# Hypnos_V3.net
KiCad netlist of a schematic drawn in EAGLE
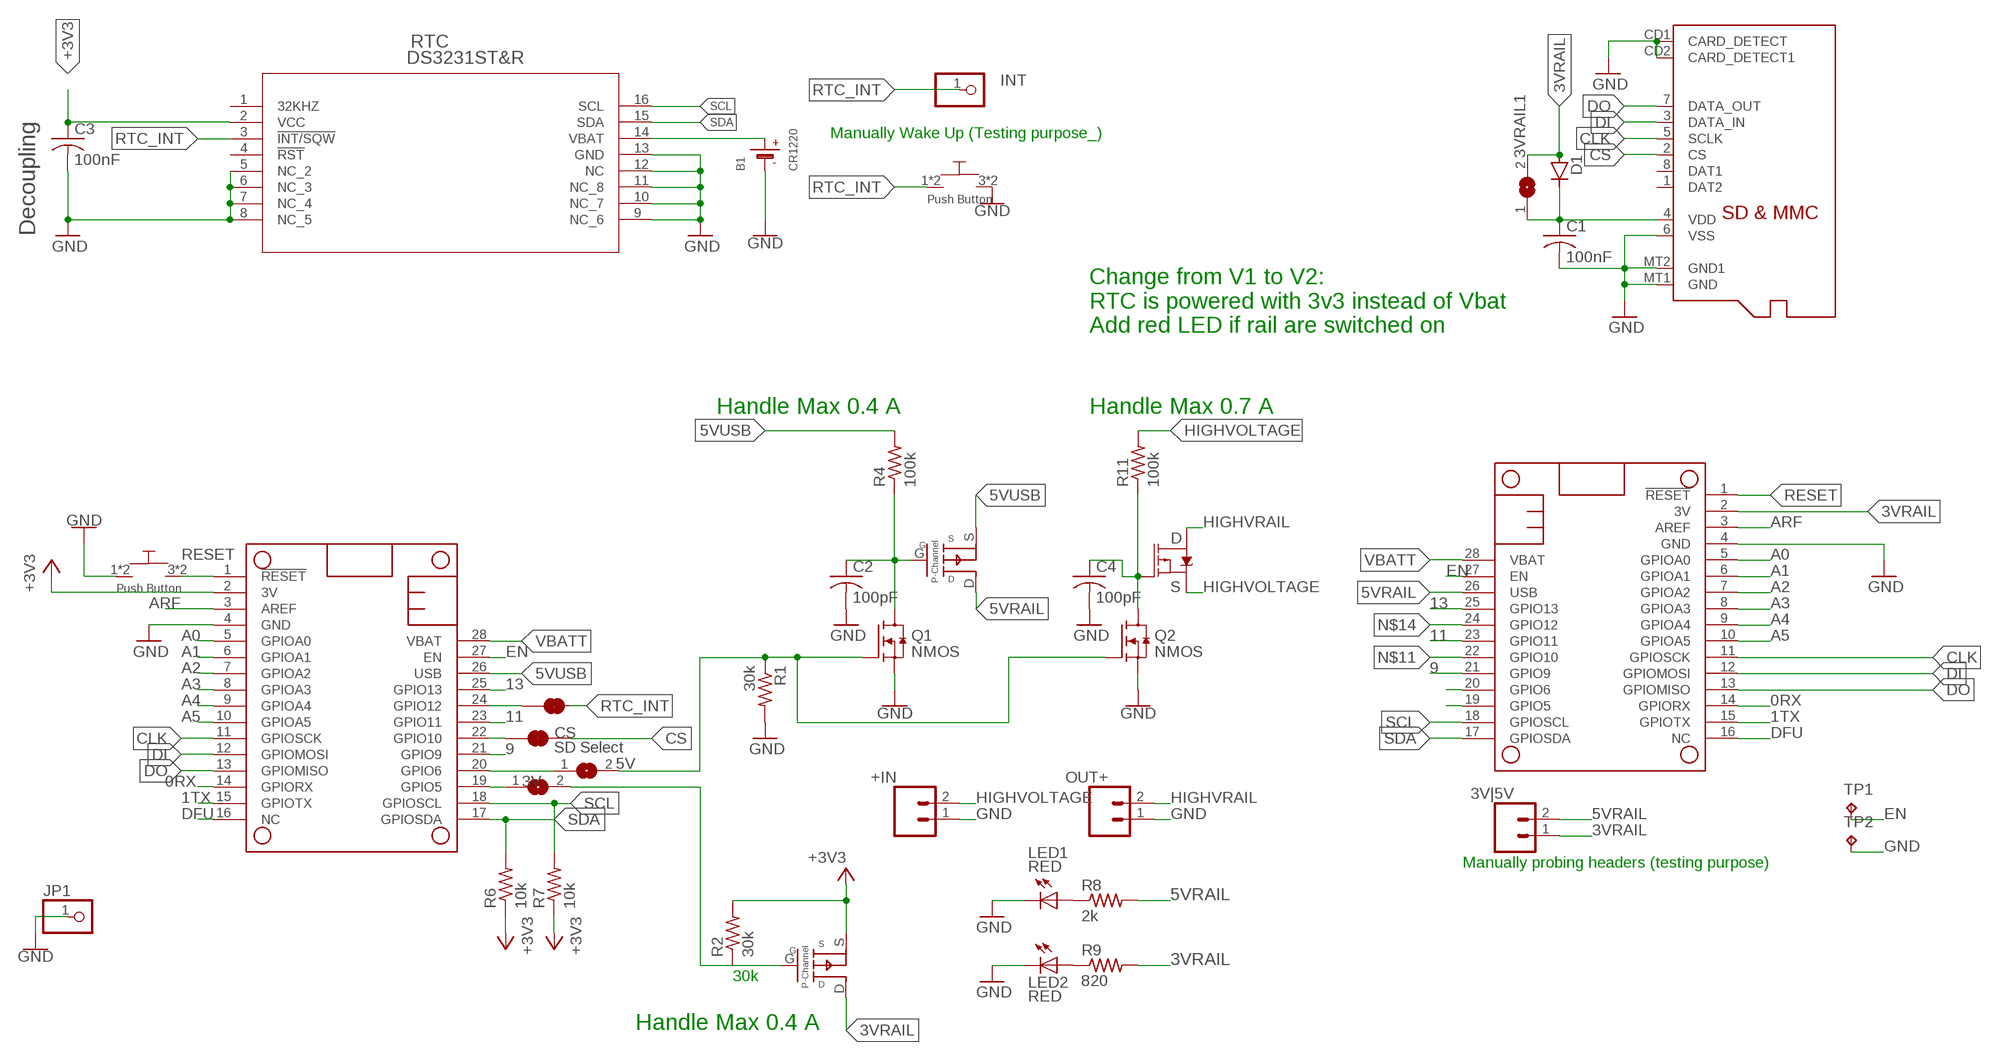
[diagram p0: schematic, sheet 1]

(export (version "E")
  (design (tool "Eeschema 10.0.6"))
  (components
    (comp (ref "+IN")
      (value "HIGHV-IN")
      (footprint "eagle-import:1X02_NO_SILK")
      (libsource (lib "eagle-import") (part "CONN_021X02_NO_SILK"))
    )
    (comp (ref "3V") (value "SJ") (footprint "eagle-import:SJ") (libsource (lib "eagle-import") (part "SJ")))
    (comp (ref "3VRAIL1")
      (value "SJ")
      (footprint "eagle-import:SJ")
      (libsource (lib "eagle-import") (part "SJ"))
    )
    (comp (ref "3V|5V")
      (value "CONN_021X02_NO_SILK")
      (footprint "eagle-import:1X02_NO_SILK")
      (libsource (lib "eagle-import") (part "CONN_021X02_NO_SILK"))
    )
    (comp (ref "5V") (value "SJ") (footprint "eagle-import:SJ") (libsource (lib "eagle-import") (part "SJ")))
    (comp (ref "B1")
      (value "CR1220")
      (footprint "eagle-import:CR1220")
      (libsource (lib "eagle-import") (part "BATTERYCR1220_SMT"))
    )
    (comp (ref "C1")
      (value "100nF")
      (footprint "eagle-import:C1206")
      (libsource (lib "eagle-import") (part "C-USC1206"))
    )
    (comp (ref "C2")
      (value "100pF")
      (footprint "eagle-import:C0805")
      (libsource (lib "eagle-import") (part "resistor_348_C-USC0805"))
    )
    (comp (ref "C3")
      (value "100nF")
      (footprint "eagle-import:C1206")
      (libsource (lib "eagle-import") (part "C-USC1206"))
    )
    (comp (ref "C4")
      (value "100pF")
      (footprint "eagle-import:C0805")
      (libsource (lib "eagle-import") (part "resistor_348_C-USC0805"))
    )
    (comp (ref "CS")
      (value "SD Select")
      (footprint "eagle-import:SMT-JUMPER_2_NC_TRACE_SILK")
      (libsource (lib "eagle-import") (part "JUMPER-SMT_2_NC_TRACE_SILK"))
    )
    (comp (ref "D1")
      (value "D-SOD123")
      (footprint "eagle-import:SOD123")
      (libsource (lib "eagle-import") (part "D-SOD123"))
    )
    (comp (ref "INT")
      (value "PINHD-1X1CB")
      (footprint "eagle-import:1X01-CLEANBIG")
      (libsource (lib "eagle-import") (part "PINHD-1X1CB"))
    )
    (comp (ref "JP1")
      (value "PINHD-1X1CB")
      (footprint "eagle-import:1X01-CLEANBIG")
      (libsource (lib "eagle-import") (part "PINHD-1X1CB"))
    )
    (comp (ref "LED1")
      (value "RED")
      (footprint "eagle-import:CHIPLED_0805")
      (libsource (lib "eagle-import") (part "LEDCHIPLED_0805"))
    )
    (comp (ref "LED2")
      (value "RED")
      (footprint "eagle-import:CHIPLED_0805")
      (libsource (lib "eagle-import") (part "LEDCHIPLED_0805"))
    )
    (comp (ref "MICROSD")
      (value "MICROSD")
      (footprint "eagle-import:MICROSD")
      (libsource (lib "eagle-import") (part "MICROSD"))
    )
    (comp (ref "MS1")
      (value "FEATHERWING")
      (footprint "eagle-import:FEATHERWING")
      (libsource (lib "eagle-import") (part "powerboard_FEATHERWING"))
    )
    (comp (ref "MS2")
      (value "FEATHERWING")
      (footprint "eagle-import:FEATHERWING")
      (libsource (lib "eagle-import") (part "FEATHERWING"))
    )
    (comp (ref "OUT+")
      (value "HIGHV-OUT")
      (footprint "eagle-import:1X02_NO_SILK")
      (libsource (lib "eagle-import") (part "CONN_021X02_NO_SILK"))
    )
    (comp (ref "PMOS1")
      (value "SSM3J3228R")
      (footprint "eagle-import:SOT-23-3")
      (libsource (lib "eagle-import") (part "SSM3J3228R"))
    )
    (comp (ref "PMOS2")
      (value "SSM3J3228R")
      (footprint "eagle-import:SOT-23-3")
      (libsource (lib "eagle-import") (part "SSM3J3228R"))
    )
    (comp (ref "PMOS3")
      (value "P-MOSFET")
      (footprint "eagle-import:SOT23-6")
      (libsource (lib "eagle-import") (part "P-MOSFET"))
    )
    (comp (ref "Q1")
      (value "NMOS")
      (footprint "eagle-import:SOT23-S")
      (libsource (lib "eagle-import") (part "NMOS"))
    )
    (comp (ref "Q2")
      (value "NMOS")
      (footprint "eagle-import:SOT23-S")
      (libsource (lib "eagle-import") (part "NMOS"))
    )
    (comp (ref "R1")
      (value "30k")
      (footprint "eagle-import:RES_1206")
      (fields
        (field (name "DIGIKEY_PART_NUMBER") "WSLP-.05TR-ND")
        (field (name "MANUFACTURER") "Vishay Dale")
        (field (name "MPN") "WSLP1206R0500FEA")
        (field (name "CREATED_BY") "PCBLayout.com")
      )
      (libsource (lib "eagle-import") (part "WSLP1206R0500FEA"))
    )
    (comp (ref "R2")
      (value "30k")
      (footprint "eagle-import:RES_1206")
      (fields
        (field (name "DIGIKEY_PART_NUMBER") "WSLP-.05TR-ND")
        (field (name "MANUFACTURER") "Vishay Dale")
        (field (name "MPN") "WSLP1206R0500FEA")
        (field (name "CREATED_BY") "PCBLayout.com")
      )
      (libsource (lib "eagle-import") (part "WSLP1206R0500FEA"))
    )
    (comp (ref "R4")
      (value "100k")
      (footprint "eagle-import:RES_1206")
      (fields
        (field (name "DIGIKEY_PART_NUMBER") "WSLP-.05TR-ND")
        (field (name "MANUFACTURER") "Vishay Dale")
        (field (name "MPN") "WSLP1206R0500FEA")
        (field (name "CREATED_BY") "PCBLayout.com")
      )
      (libsource (lib "eagle-import") (part "WSLP1206R0500FEA"))
    )
    (comp (ref "R6")
      (value "10k")
      (footprint "eagle-import:RES_1206")
      (fields
        (field (name "DIGIKEY_PART_NUMBER") "WSLP-.05TR-ND")
        (field (name "MANUFACTURER") "Vishay Dale")
        (field (name "MPN") "WSLP1206R0500FEA")
        (field (name "CREATED_BY") "PCBLayout.com")
      )
      (libsource (lib "eagle-import") (part "WSLP1206R0500FEA"))
    )
    (comp (ref "R7")
      (value "10k")
      (footprint "eagle-import:RES_1206")
      (fields
        (field (name "DIGIKEY_PART_NUMBER") "WSLP-.05TR-ND")
        (field (name "MANUFACTURER") "Vishay Dale")
        (field (name "MPN") "WSLP1206R0500FEA")
        (field (name "CREATED_BY") "PCBLayout.com")
      )
      (libsource (lib "eagle-import") (part "WSLP1206R0500FEA"))
    )
    (comp (ref "R8")
      (value "2k")
      (footprint "eagle-import:RES_1206")
      (fields
        (field (name "DIGIKEY_PART_NUMBER") "WSLP-.05TR-ND")
        (field (name "MANUFACTURER") "Vishay Dale")
        (field (name "MPN") "WSLP1206R0500FEA")
        (field (name "CREATED_BY") "PCBLayout.com")
      )
      (libsource (lib "eagle-import") (part "WSLP1206R0500FEA"))
    )
    (comp (ref "R9")
      (value "820")
      (footprint "eagle-import:RES_1206")
      (fields
        (field (name "DIGIKEY_PART_NUMBER") "WSLP-.05TR-ND")
        (field (name "MANUFACTURER") "Vishay Dale")
        (field (name "MPN") "WSLP1206R0500FEA")
        (field (name "CREATED_BY") "PCBLayout.com")
      )
      (libsource (lib "eagle-import") (part "WSLP1206R0500FEA"))
    )
    (comp (ref "R11")
      (value "100k")
      (footprint "eagle-import:RES_1206")
      (fields
        (field (name "DIGIKEY_PART_NUMBER") "WSLP-.05TR-ND")
        (field (name "MANUFACTURER") "Vishay Dale")
        (field (name "MPN") "WSLP1206R0500FEA")
        (field (name "CREATED_BY") "PCBLayout.com")
      )
      (libsource (lib "eagle-import") (part "WSLP1206R0500FEA"))
    )
    (comp (ref "RTC")
      (value "DS3231ST&R")
      (footprint "eagle-import:21-0042B_16")
      (fields (field (name "MANUFACTURER_PART_NUMBER") "DS3231S#T&R"))
      (libsource (lib "eagle-import") (part "DS3231ST&R"))
    )
    (comp (ref "RTC_INT")
      (value "JUMPER-SMT_2_NC_TRACE_SILK")
      (footprint "eagle-import:SMT-JUMPER_2_NC_TRACE_SILK")
      (libsource (lib "eagle-import") (part "JUMPER-SMT_2_NC_TRACE_SILK"))
    )
    (comp (ref "TP1")
      (value "TPTP16R")
      (footprint "eagle-import:TP16R")
      (libsource (lib "eagle-import") (part "TPTP16R"))
    )
    (comp (ref "TP2")
      (value "TPTP16R")
      (footprint "eagle-import:TP16R")
      (libsource (lib "eagle-import") (part "TPTP16R"))
    )
    (comp (ref "U$1")
      (value "PUSH_BUTTON")
      (footprint "eagle-import:PUSHBUTTON_SMD")
      (libsource (lib "eagle-import") (part "PUSH_BUTTON"))
    )
    (comp (ref "U$2")
      (value "PUSH_BUTTON")
      (footprint "eagle-import:PUSHBUTTON_SMD")
      (libsource (lib "eagle-import") (part "PUSH_BUTTON"))
    )
  )
  (nets
    (net (code "1") (name "+3V3") (class "Default")
      (node (ref "C3") (pin "1") (pinfunction "1_1") (pintype "passive"))
      (node (ref "MS2") (pin "2") (pinfunction "3V_2") (pintype "power_in"))
      (node (ref "PMOS2") (pin "S") (pinfunction "S_S") (pintype "bidirectional"))
      (node (ref "R2") (pin "2") (pinfunction "2_2") (pintype "passive"))
      (node (ref "R6") (pin "1") (pinfunction "1_1") (pintype "passive"))
      (node (ref "R7") (pin "1") (pinfunction "1_1") (pintype "passive"))
      (node (ref "RTC") (pin "2") (pinfunction "VCC_2") (pintype "power_in"))
    )
    (net (code "2") (name "/0RX") (class "Default")
      (node (ref "MS1") (pin "14") (pinfunction "GPIORX_14") (pintype "bidirectional"))
      (node (ref "MS2") (pin "14") (pinfunction "GPIORX_14") (pintype "bidirectional"))
    )
    (net (code "3") (name "/1TX") (class "Default")
      (node (ref "MS1") (pin "15") (pinfunction "GPIOTX_15") (pintype "bidirectional"))
      (node (ref "MS2") (pin "15") (pinfunction "GPIOTX_15") (pintype "bidirectional"))
    )
    (net (code "4") (name "/9") (class "Default")
      (node (ref "MS1") (pin "21") (pinfunction "GPIO9_21") (pintype "bidirectional"))
      (node (ref "MS2") (pin "21") (pinfunction "GPIO9_21") (pintype "bidirectional"))
    )
    (net (code "5") (name "/11") (class "Default")
      (node (ref "MS1") (pin "23") (pinfunction "GPIO11_23") (pintype "bidirectional"))
      (node (ref "MS2") (pin "23") (pinfunction "GPIO11_23") (pintype "bidirectional"))
    )
    (net (code "6") (name "/13") (class "Default")
      (node (ref "MS1") (pin "25") (pinfunction "GPIO13_25") (pintype "bidirectional"))
      (node (ref "MS2") (pin "25") (pinfunction "GPIO13_25") (pintype "bidirectional"))
    )
    (net (code "7") (name "/A0") (class "Default")
      (node (ref "MS1") (pin "5") (pinfunction "GPIOA0_5") (pintype "bidirectional"))
      (node (ref "MS2") (pin "5") (pinfunction "GPIOA0_5") (pintype "bidirectional"))
    )
    (net (code "8") (name "/A1") (class "Default")
      (node (ref "MS1") (pin "6") (pinfunction "GPIOA1_6") (pintype "bidirectional"))
      (node (ref "MS2") (pin "6") (pinfunction "GPIOA1_6") (pintype "bidirectional"))
    )
    (net (code "9") (name "/A2") (class "Default")
      (node (ref "MS1") (pin "7") (pinfunction "GPIOA2_7") (pintype "bidirectional"))
      (node (ref "MS2") (pin "7") (pinfunction "GPIOA2_7") (pintype "bidirectional"))
    )
    (net (code "10") (name "/A3") (class "Default")
      (node (ref "MS1") (pin "8") (pinfunction "GPIOA3_8") (pintype "bidirectional"))
      (node (ref "MS2") (pin "8") (pinfunction "GPIOA3_8") (pintype "bidirectional"))
    )
    (net (code "11") (name "/A4") (class "Default")
      (node (ref "MS1") (pin "9") (pinfunction "GPIOA4_9") (pintype "bidirectional"))
      (node (ref "MS2") (pin "9") (pinfunction "GPIOA4_9") (pintype "bidirectional"))
    )
    (net (code "12") (name "/A5") (class "Default")
      (node (ref "MS1") (pin "10") (pinfunction "GPIOA5_10") (pintype "bidirectional"))
      (node (ref "MS2") (pin "10") (pinfunction "GPIOA5_10") (pintype "bidirectional"))
    )
    (net (code "13") (name "/ARF") (class "Default")
      (node (ref "MS1") (pin "3") (pinfunction "AREF_3") (pintype "passive"))
      (node (ref "MS2") (pin "3") (pinfunction "AREF_3") (pintype "passive"))
    )
    (net (code "14") (name "/DFU") (class "Default")
      (node (ref "MS1") (pin "16") (pinfunction "NC_16") (pintype "passive"))
      (node (ref "MS2") (pin "16") (pinfunction "NC_16") (pintype "passive"))
    )
    (net (code "15") (name "/EN") (class "Default")
      (node (ref "MS1") (pin "27") (pinfunction "EN_27") (pintype "passive"))
      (node (ref "MS2") (pin "27") (pinfunction "EN_27") (pintype "passive"))
      (node (ref "TP1") (pin "TP") (pinfunction "TP_TP") (pintype "input"))
    )
    (net (code "16") (name "/HIGHVRAIL") (class "Default")
      (node (ref "OUT+") (pin "2") (pinfunction "2_2") (pintype "passive"))
      (node (ref "PMOS3") (pin "1") (pinfunction "D_1") (pintype "bidirectional"))
      (node (ref "PMOS3") (pin "2") (pinfunction "D_2") (pintype "bidirectional"))
      (node (ref "PMOS3") (pin "5") (pinfunction "D_5") (pintype "bidirectional"))
      (node (ref "PMOS3") (pin "6") (pinfunction "D_6") (pintype "bidirectional"))
    )
    (net (code "17") (name "3VRAIL") (class "Default")
      (node (ref "3VRAIL1") (pin "2") (pinfunction "2_2") (pintype "passive"))
      (node (ref "3V|5V") (pin "1") (pinfunction "1_1") (pintype "passive"))
      (node (ref "D1") (pin "2") (pinfunction "A_2") (pintype "passive"))
      (node (ref "MS1") (pin "2") (pinfunction "3V_2") (pintype "power_in"))
      (node (ref "PMOS2") (pin "D") (pinfunction "D_D") (pintype "bidirectional"))
      (node (ref "R9") (pin "2") (pinfunction "2_2") (pintype "passive"))
    )
    (net (code "18") (name "5VRAIL") (class "Default")
      (node (ref "3V|5V") (pin "2") (pinfunction "2_2") (pintype "passive"))
      (node (ref "MS1") (pin "26") (pinfunction "USB_26") (pintype "power_in"))
      (node (ref "PMOS1") (pin "D") (pinfunction "D_D") (pintype "bidirectional"))
      (node (ref "R8") (pin "2") (pinfunction "2_2") (pintype "passive"))
    )
    (net (code "19") (name "5VUSB") (class "Default")
      (node (ref "MS2") (pin "26") (pinfunction "USB_26") (pintype "power_in"))
      (node (ref "PMOS1") (pin "S") (pinfunction "S_S") (pintype "bidirectional"))
      (node (ref "R4") (pin "2") (pinfunction "2_2") (pintype "passive"))
    )
    (net (code "20") (name "CLK") (class "Default")
      (node (ref "MICROSD") (pin "5") (pinfunction "SCLK_5") (pintype "input"))
      (node (ref "MS1") (pin "11") (pinfunction "GPIOSCK_11") (pintype "bidirectional"))
      (node (ref "MS2") (pin "11") (pinfunction "GPIOSCK_11") (pintype "bidirectional"))
    )
    (net (code "21") (name "CS") (class "Default")
      (node (ref "CS") (pin "2") (pinfunction "2_2") (pintype "passive"))
      (node (ref "MICROSD") (pin "2") (pinfunction "CS_2") (pintype "input"))
    )
    (net (code "22") (name "DI") (class "Default")
      (node (ref "MICROSD") (pin "3") (pinfunction "DATA_IN_3") (pintype "input"))
      (node (ref "MS1") (pin "12") (pinfunction "GPIOMOSI_12") (pintype "bidirectional"))
      (node (ref "MS2") (pin "12") (pinfunction "GPIOMOSI_12") (pintype "bidirectional"))
    )
    (net (code "23") (name "DO") (class "Default")
      (node (ref "MICROSD") (pin "7") (pinfunction "DATA_OUT_7") (pintype "output"))
      (node (ref "MS1") (pin "13") (pinfunction "GPIOMISO_13") (pintype "bidirectional"))
      (node (ref "MS2") (pin "13") (pinfunction "GPIOMISO_13") (pintype "bidirectional"))
    )
    (net (code "24") (name "GND") (class "Default")
      (node (ref "+IN") (pin "1") (pinfunction "1_1") (pintype "passive"))
      (node (ref "B1") (pin "-") (pinfunction "-_-") (pintype "passive"))
      (node (ref "C1") (pin "2") (pinfunction "2_2") (pintype "passive"))
      (node (ref "C2") (pin "2") (pinfunction "2_2") (pintype "passive"))
      (node (ref "C3") (pin "2") (pinfunction "2_2") (pintype "passive"))
      (node (ref "C4") (pin "2") (pinfunction "2_2") (pintype "passive"))
      (node (ref "JP1") (pin "1") (pinfunction "1_1") (pintype "passive"))
      (node (ref "LED1") (pin "C") (pinfunction "C_C") (pintype "passive"))
      (node (ref "LED2") (pin "C") (pinfunction "C_C") (pintype "passive"))
      (node (ref "MICROSD") (pin "6") (pinfunction "VSS_6") (pintype "power_in"))
      (node (ref "MICROSD") (pin "CD1") (pinfunction "CARD_DETECT_CD1") (pintype "passive"))
      (node (ref "MICROSD") (pin "CD2") (pinfunction "CARD_DETECT1_CD2") (pintype "passive"))
      (node (ref "MICROSD") (pin "MT1") (pinfunction "GND_MT1") (pintype "power_in"))
      (node (ref "MICROSD") (pin "MT2") (pinfunction "GND1_MT2") (pintype "power_in"))
      (node (ref "MS1") (pin "4") (pinfunction "GND_4") (pintype "power_in"))
      (node (ref "MS2") (pin "4") (pinfunction "GND_4") (pintype "power_in"))
      (node (ref "OUT+") (pin "1") (pinfunction "1_1") (pintype "passive"))
      (node (ref "Q1") (pin "2") (pinfunction "S_2") (pintype "passive"))
      (node (ref "Q2") (pin "2") (pinfunction "S_2") (pintype "passive"))
      (node (ref "R1") (pin "2") (pinfunction "2_2") (pintype "passive"))
      (node (ref "RTC") (pin "10") (pinfunction "NC_7_10") (pintype "passive"))
      (node (ref "RTC") (pin "11") (pinfunction "NC_8_11") (pintype "passive"))
      (node (ref "RTC") (pin "12") (pinfunction "NC_12") (pintype "passive"))
      (node (ref "RTC") (pin "13") (pinfunction "GND_13") (pintype "power_in"))
      (node (ref "RTC") (pin "5") (pinfunction "NC_2_5") (pintype "passive"))
      (node (ref "RTC") (pin "6") (pinfunction "NC_3_6") (pintype "passive"))
      (node (ref "RTC") (pin "7") (pinfunction "NC_4_7") (pintype "passive"))
      (node (ref "RTC") (pin "8") (pinfunction "NC_5_8") (pintype "passive"))
      (node (ref "RTC") (pin "9") (pinfunction "NC_6_9") (pintype "passive"))
      (node (ref "TP2") (pin "TP") (pinfunction "TP_TP") (pintype "input"))
      (node (ref "U$1") (pin "1") (pinfunction "P$1_1") (pintype "bidirectional"))
      (node (ref "U$1") (pin "2") (pinfunction "P$1_2") (pintype "bidirectional"))
      (node (ref "U$2") (pin "3") (pinfunction "P$2_3") (pintype "bidirectional"))
      (node (ref "U$2") (pin "4") (pinfunction "P$2_4") (pintype "bidirectional"))
    )
    (net (code "25") (name "HIGHVOLTAGE") (class "Default")
      (node (ref "+IN") (pin "2") (pinfunction "2_2") (pintype "passive"))
      (node (ref "PMOS3") (pin "4") (pinfunction "S_4") (pintype "bidirectional"))
      (node (ref "R11") (pin "2") (pinfunction "2_2") (pintype "passive"))
    )
    (net (code "26") (name "N$11") (class "Default")
      (node (ref "CS") (pin "1") (pinfunction "1_1") (pintype "passive"))
      (node (ref "MS1") (pin "22") (pinfunction "GPIO10_22") (pintype "bidirectional"))
      (node (ref "MS2") (pin "22") (pinfunction "GPIO10_22") (pintype "bidirectional"))
    )
    (net (code "27") (name "N$14") (class "Default")
      (node (ref "MS1") (pin "24") (pinfunction "GPIO12_24") (pintype "bidirectional"))
      (node (ref "MS2") (pin "24") (pinfunction "GPIO12_24") (pintype "bidirectional"))
      (node (ref "RTC_INT") (pin "1") (pinfunction "1_1") (pintype "passive"))
    )
    (net (code "28") (name "Net-(3V-Pad2)") (class "Default")
      (node (ref "3V") (pin "2") (pinfunction "2_2") (pintype "passive"))
      (node (ref "PMOS2") (pin "G") (pinfunction "G_G") (pintype "bidirectional"))
      (node (ref "R2") (pin "1") (pinfunction "1_1") (pintype "passive"))
    )
    (net (code "29") (name "Net-(B1-+)") (class "Default")
      (node (ref "B1") (pin "+$1") (pinfunction "+_+$1") (pintype "passive"))
      (node (ref "RTC") (pin "14") (pinfunction "VBAT_14") (pintype "power_in"))
    )
    (net (code "30") (name "Net-(D1-C)") (class "Default")
      (node (ref "3VRAIL1") (pin "1") (pinfunction "1_1") (pintype "passive"))
      (node (ref "C1") (pin "1") (pinfunction "1_1") (pintype "passive"))
      (node (ref "D1") (pin "1") (pinfunction "C_1") (pintype "passive"))
      (node (ref "MICROSD") (pin "4") (pinfunction "VDD_4") (pintype "power_in"))
    )
    (net (code "31") (name "Net-(LED1-PadA)") (class "Default")
      (node (ref "LED1") (pin "A") (pinfunction "A_A") (pintype "passive"))
      (node (ref "R8") (pin "1") (pinfunction "1_1") (pintype "passive"))
    )
    (net (code "32") (name "Net-(LED2-PadA)") (class "Default")
      (node (ref "LED2") (pin "A") (pinfunction "A_A") (pintype "passive"))
      (node (ref "R9") (pin "1") (pinfunction "1_1") (pintype "passive"))
    )
    (net (code "33") (name "Net-(MS2-GPIO5)") (class "Default")
      (node (ref "3V") (pin "1") (pinfunction "1_1") (pintype "passive"))
      (node (ref "MS2") (pin "19") (pinfunction "GPIO5_19") (pintype "bidirectional"))
    )
    (net (code "34") (name "Net-(MS2-GPIO6)") (class "Default")
      (node (ref "5V") (pin "1") (pinfunction "1_1") (pintype "passive"))
      (node (ref "MS2") (pin "20") (pinfunction "GPIO6_20") (pintype "bidirectional"))
    )
    (net (code "35") (name "Net-(PMOS3-G)") (class "Default")
      (node (ref "C4") (pin "1") (pinfunction "1_1") (pintype "passive"))
      (node (ref "PMOS3") (pin "3") (pinfunction "G_3") (pintype "bidirectional"))
      (node (ref "Q2") (pin "3") (pinfunction "D_3") (pintype "passive"))
      (node (ref "R11") (pin "1") (pinfunction "1_1") (pintype "passive"))
    )
    (net (code "36") (name "Net-(Q1-D)") (class "Default")
      (node (ref "C2") (pin "1") (pinfunction "1_1") (pintype "passive"))
      (node (ref "PMOS1") (pin "G") (pinfunction "G_G") (pintype "bidirectional"))
      (node (ref "Q1") (pin "3") (pinfunction "D_3") (pintype "passive"))
      (node (ref "R4") (pin "1") (pinfunction "1_1") (pintype "passive"))
    )
    (net (code "37") (name "Net-(Q1-G)") (class "Default")
      (node (ref "5V") (pin "2") (pinfunction "2_2") (pintype "passive"))
      (node (ref "Q1") (pin "1") (pinfunction "G_1") (pintype "passive"))
      (node (ref "Q2") (pin "1") (pinfunction "G_1") (pintype "passive"))
      (node (ref "R1") (pin "1") (pinfunction "1_1") (pintype "passive"))
    )
    (net (code "38") (name "RESET") (class "Default")
      (node (ref "MS1") (pin "1") (pinfunction "~{RESET}_1") (pintype "input"))
      (node (ref "MS2") (pin "1") (pinfunction "~{RESET}_1") (pintype "input"))
      (node (ref "U$1") (pin "3") (pinfunction "P$2_3") (pintype "bidirectional"))
      (node (ref "U$1") (pin "4") (pinfunction "P$2_4") (pintype "bidirectional"))
    )
    (net (code "39") (name "RTC_INT") (class "Default")
      (node (ref "INT") (pin "1") (pinfunction "1_1") (pintype "passive"))
      (node (ref "RTC") (pin "3") (pinfunction "~{INT/SQW}_3") (pintype "passive"))
      (node (ref "RTC_INT") (pin "2") (pinfunction "2_2") (pintype "passive"))
      (node (ref "U$2") (pin "1") (pinfunction "P$1_1") (pintype "bidirectional"))
      (node (ref "U$2") (pin "2") (pinfunction "P$1_2") (pintype "bidirectional"))
    )
    (net (code "40") (name "SCL") (class "Default")
      (node (ref "MS1") (pin "18") (pinfunction "GPIOSCL_18") (pintype "bidirectional"))
      (node (ref "MS2") (pin "18") (pinfunction "GPIOSCL_18") (pintype "bidirectional"))
      (node (ref "R7") (pin "2") (pinfunction "2_2") (pintype "passive"))
      (node (ref "RTC") (pin "16") (pinfunction "SCL_16") (pintype "passive"))
    )
    (net (code "41") (name "SDA") (class "Default")
      (node (ref "MS1") (pin "17") (pinfunction "GPIOSDA_17") (pintype "bidirectional"))
      (node (ref "MS2") (pin "17") (pinfunction "GPIOSDA_17") (pintype "bidirectional"))
      (node (ref "R6") (pin "2") (pinfunction "2_2") (pintype "passive"))
      (node (ref "RTC") (pin "15") (pinfunction "SDA_15") (pintype "passive"))
    )
    (net (code "42") (name "VBATT") (class "Default")
      (node (ref "MS1") (pin "28") (pinfunction "VBAT_28") (pintype "power_in"))
      (node (ref "MS2") (pin "28") (pinfunction "VBAT_28") (pintype "power_in"))
    )
    (net (code "43") (name "unconnected-(MICROSD-DAT1-Pad8)") (class "Default")
      (node (ref "MICROSD") (pin "8") (pinfunction "DAT1_8") (pintype "bidirectional"))
    )
    (net (code "44") (name "unconnected-(MICROSD-DAT2-Pad1)") (class "Default")
      (node (ref "MICROSD") (pin "1") (pinfunction "DAT2_1") (pintype "bidirectional"))
    )
    (net (code "45") (name "unconnected-(MS1-GPIO5-Pad19)") (class "Default")
      (node (ref "MS1") (pin "19") (pinfunction "GPIO5_19") (pintype "bidirectional"))
    )
    (net (code "46") (name "unconnected-(MS1-GPIO6-Pad20)") (class "Default")
      (node (ref "MS1") (pin "20") (pinfunction "GPIO6_20") (pintype "bidirectional"))
    )
    (net (code "47") (name "unconnected-(RTC-32KHZ-Pad1)") (class "Default")
      (node (ref "RTC") (pin "1") (pinfunction "32KHZ_1") (pintype "passive"))
    )
    (net (code "48") (name "unconnected-(RTC-~{RST}-Pad4)") (class "Default")
      (node (ref "RTC") (pin "4") (pinfunction "~{RST}_4") (pintype "passive"))
    )
  )
)
